# Ultrasonic_Receiver.net
KiCad netlist of a schematic drawn in Altium Designer
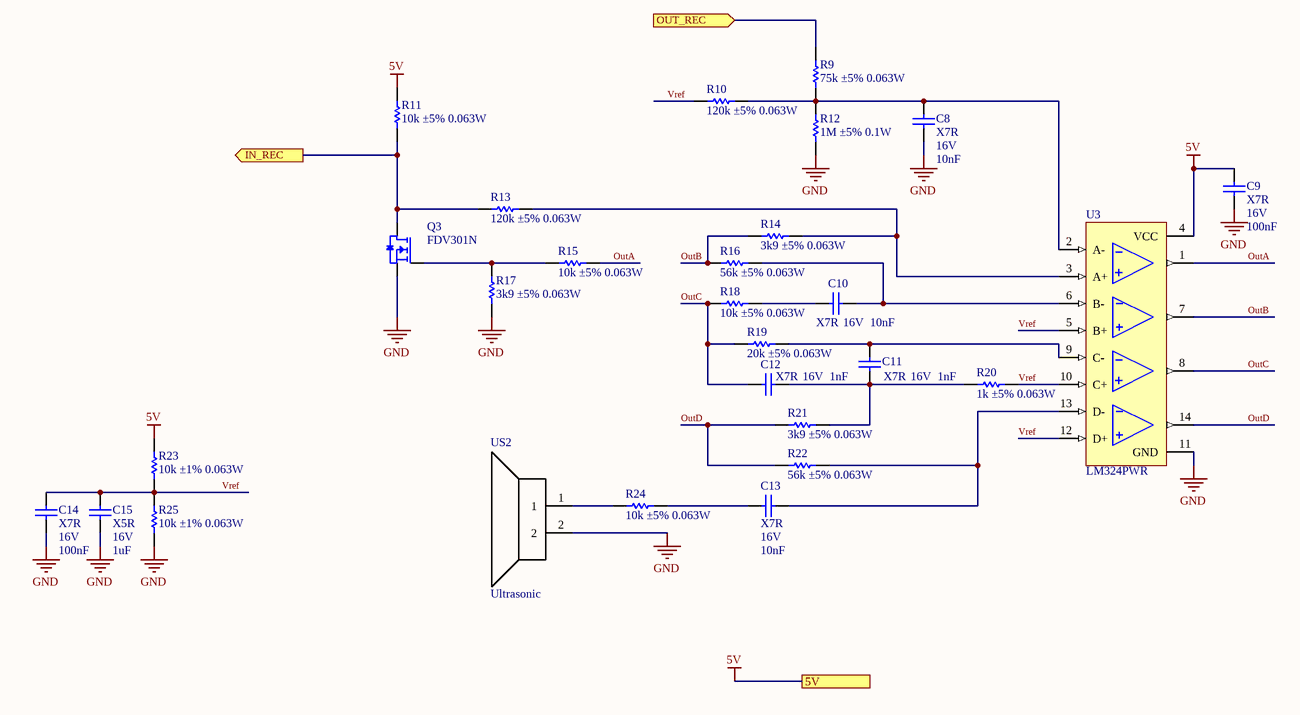
[diagram p0: Ultrasonic_Receiver.SchDoc]

(export (version "E")
  (design (tool "Eeschema 10.0.6"))
  (components
    (comp (ref "C8")
      (value "Capacitor")
      (footprint "C0402")
      (description "Capacitor SMD")
      (fields
        (field (name "DIELECTRIC") "X7R")
        (field (name "VOLTAGE") "16V")
        (field (name "CAPACITANCE") "10nF")
        (field (name "PART NUMBER") "C0402_10nF_16V_±10%")
        (field (name "TOLERANCE") "±10%")
      )
      (libsource (lib "Pasives_Capacitor_SMD") (part "Capacitor"))
    )
    (comp (ref "C9")
      (value "Capacitor")
      (footprint "C0402")
      (description "Capacitor SMD")
      (fields
        (field (name "DIELECTRIC") "X7R")
        (field (name "VOLTAGE") "16V")
        (field (name "CAPACITANCE") "100nF")
        (field (name "PART NUMBER") "C0402_100nF_16V_±10%")
        (field (name "TOLERANCE") "±10%")
      )
      (libsource (lib "Pasives_Capacitor_SMD") (part "Capacitor"))
    )
    (comp (ref "C10")
      (value "Capacitor")
      (footprint "C0402")
      (description "Capacitor SMD")
      (fields
        (field (name "DIELECTRIC") "X7R")
        (field (name "VOLTAGE") "16V")
        (field (name "CAPACITANCE") "10nF")
        (field (name "PART NUMBER") "C0402_10nF_16V_±10%")
        (field (name "TOLERANCE") "±10%")
      )
      (libsource (lib "Pasives_Capacitor_SMD") (part "Capacitor"))
    )
    (comp (ref "C11")
      (value "Capacitor")
      (footprint "C0402")
      (description "Capacitor SMD")
      (fields
        (field (name "DIELECTRIC") "X7R")
        (field (name "VOLTAGE") "16V")
        (field (name "CAPACITANCE") "1nF")
        (field (name "PART NUMBER") "C0402_1nF_16V_±10%")
        (field (name "TOLERANCE") "±10%")
      )
      (libsource (lib "Pasives_Capacitor_SMD") (part "Capacitor"))
    )
    (comp (ref "C12")
      (value "Capacitor")
      (footprint "C0402")
      (description "Capacitor SMD")
      (fields
        (field (name "DIELECTRIC") "X7R")
        (field (name "VOLTAGE") "16V")
        (field (name "CAPACITANCE") "1nF")
        (field (name "PART NUMBER") "C0402_1nF_16V_±10%")
        (field (name "TOLERANCE") "±10%")
      )
      (libsource (lib "Pasives_Capacitor_SMD") (part "Capacitor"))
    )
    (comp (ref "C13")
      (value "Capacitor")
      (footprint "C0402")
      (description "Capacitor SMD")
      (fields
        (field (name "DIELECTRIC") "X7R")
        (field (name "VOLTAGE") "16V")
        (field (name "CAPACITANCE") "10nF")
        (field (name "PART NUMBER") "C0402_10nF_16V_±10%")
        (field (name "TOLERANCE") "±10%")
      )
      (libsource (lib "Pasives_Capacitor_SMD") (part "Capacitor"))
    )
    (comp (ref "C14")
      (value "Capacitor")
      (footprint "C0402")
      (description "Capacitor SMD")
      (fields
        (field (name "DIELECTRIC") "X7R")
        (field (name "VOLTAGE") "16V")
        (field (name "CAPACITANCE") "100nF")
        (field (name "PART NUMBER") "C0402_100nF_16V_±10%")
        (field (name "TOLERANCE") "±10%")
      )
      (libsource (lib "Pasives_Capacitor_SMD") (part "Capacitor"))
    )
    (comp (ref "C15")
      (value "Capacitor")
      (footprint "C0603")
      (description "Capacitor SMD")
      (fields
        (field (name "DIELECTRIC") "X5R")
        (field (name "VOLTAGE") "16V")
        (field (name "CAPACITANCE") "1uF")
        (field (name "PART NUMBER") "C0603_1uF_16V_±10%")
        (field (name "TOLERANCE") "±10%")
      )
      (libsource (lib "Pasives_Capacitor_SMD") (part "Capacitor"))
    )
    (comp (ref "Q3")
      (value "FDV301N")
      (footprint "SOT23-3")
      (description "NFET")
      (fields (field (name "MANUFACTURER") "Fairchild Semiconductor"))
      (libsource (lib "Semiconductors_Transistors") (part "Mosfet_N"))
    )
    (comp (ref "R9")
      (value "75k ±5% 0.063W")
      (footprint "R0402")
      (description "Resistor, SMD")
      (fields (field (name "TOLERANCE") "±5%") (field (name "POWER") "0.063W"))
      (libsource (lib "Pasives_Resistor_SMD") (part "Resistor"))
    )
    (comp (ref "R10")
      (value "120k ±5% 0.063W")
      (footprint "R0402")
      (description "Resistor, SMD")
      (fields (field (name "TOLERANCE") "±5%") (field (name "POWER") "0.063W"))
      (libsource (lib "Pasives_Resistor_SMD") (part "Resistor"))
    )
    (comp (ref "R11")
      (value "10k ±5% 0.063W")
      (footprint "R0402")
      (description "Resistor, SMD")
      (fields (field (name "TOLERANCE") "±5%") (field (name "POWER") "0.063W"))
      (libsource (lib "Pasives_Resistor_SMD") (part "Resistor"))
    )
    (comp (ref "R12")
      (value "1M ±5% 0.1W")
      (footprint "R0603")
      (description "Resistor, SMD")
      (fields (field (name "TOLERANCE") "±5%") (field (name "POWER") "0.1W"))
      (libsource (lib "Pasives_Resistor_SMD") (part "Resistor"))
    )
    (comp (ref "R13")
      (value "120k ±5% 0.063W")
      (footprint "R0402")
      (description "Resistor, SMD")
      (fields (field (name "TOLERANCE") "±5%") (field (name "POWER") "0.063W"))
      (libsource (lib "Pasives_Resistor_SMD") (part "Resistor"))
    )
    (comp (ref "R14")
      (value "3k9 ±5% 0.063W")
      (footprint "R0402")
      (description "Resistor, SMD")
      (fields (field (name "TOLERANCE") "±5%") (field (name "POWER") "0.063W"))
      (libsource (lib "Pasives_Resistor_SMD") (part "Resistor"))
    )
    (comp (ref "R15")
      (value "10k ±5% 0.063W")
      (footprint "R0402")
      (description "Resistor, SMD")
      (fields (field (name "TOLERANCE") "±5%") (field (name "POWER") "0.063W"))
      (libsource (lib "Pasives_Resistor_SMD") (part "Resistor"))
    )
    (comp (ref "R16")
      (value "56k ±5% 0.063W")
      (footprint "R0402")
      (description "Resistor, SMD")
      (fields (field (name "TOLERANCE") "±5%") (field (name "POWER") "0.063W"))
      (libsource (lib "Pasives_Resistor_SMD") (part "Resistor"))
    )
    (comp (ref "R17")
      (value "3k9 ±5% 0.063W")
      (footprint "R0402")
      (description "Resistor, SMD")
      (fields (field (name "TOLERANCE") "±5%") (field (name "POWER") "0.063W"))
      (libsource (lib "Pasives_Resistor_SMD") (part "Resistor"))
    )
    (comp (ref "R18")
      (value "10k ±5% 0.063W")
      (footprint "R0402")
      (description "Resistor, SMD")
      (fields (field (name "TOLERANCE") "±5%") (field (name "POWER") "0.063W"))
      (libsource (lib "Pasives_Resistor_SMD") (part "Resistor"))
    )
    (comp (ref "R19")
      (value "20k ±5% 0.063W")
      (footprint "R0402")
      (description "Resistor, SMD")
      (fields (field (name "TOLERANCE") "±5%") (field (name "POWER") "0.063W"))
      (libsource (lib "Pasives_Resistor_SMD") (part "Resistor"))
    )
    (comp (ref "R20")
      (value "1k ±5% 0.063W")
      (footprint "R0402")
      (description "Resistor, SMD")
      (fields (field (name "TOLERANCE") "±5%") (field (name "POWER") "0.063W"))
      (libsource (lib "Pasives_Resistor_SMD") (part "Resistor"))
    )
    (comp (ref "R21")
      (value "3k9 ±5% 0.063W")
      (footprint "R0402")
      (description "Resistor, SMD")
      (fields (field (name "TOLERANCE") "±5%") (field (name "POWER") "0.063W"))
      (libsource (lib "Pasives_Resistor_SMD") (part "Resistor"))
    )
    (comp (ref "R22")
      (value "56k ±5% 0.063W")
      (footprint "R0402")
      (description "Resistor, SMD")
      (fields (field (name "TOLERANCE") "±5%") (field (name "POWER") "0.063W"))
      (libsource (lib "Pasives_Resistor_SMD") (part "Resistor"))
    )
    (comp (ref "R23")
      (value "10k ±1% 0.063W")
      (footprint "R0402")
      (description "Resistor, SMD")
      (fields (field (name "TOLERANCE") "±1%") (field (name "POWER") "0.063W"))
      (libsource (lib "Pasives_Resistor_SMD") (part "Resistor"))
    )
    (comp (ref "R24")
      (value "10k ±5% 0.063W")
      (footprint "R0402")
      (description "Resistor, SMD")
      (fields (field (name "TOLERANCE") "±5%") (field (name "POWER") "0.063W"))
      (libsource (lib "Pasives_Resistor_SMD") (part "Resistor"))
    )
    (comp (ref "R25")
      (value "10k ±1% 0.063W")
      (footprint "R0402")
      (description "Resistor, SMD")
      (fields (field (name "TOLERANCE") "±1%") (field (name "POWER") "0.063W"))
      (libsource (lib "Pasives_Resistor_SMD") (part "Resistor"))
    )
    (comp (ref "U3")
      (value "LM324PWR")
      (footprint "TSSOP14")
      (description "Operational Amplifier Quadruple")
      (fields (field (name "MANUFACTURER") "Texas Instruments"))
      (libsource (lib "Semiconductors_OA") (part "LM324PWR"))
    )
    (comp (ref "US2")
      (value "Ultrasonic")
      (footprint "NU40C16")
      (description "Ultrasonic Sensor")
      (fields (field (name "PART NUMBER") "NU40C16R-2") (field (name "MANUFACTURER") "Jinci"))
      (libsource (lib "Sensors") (part "Ultrasonic"))
    )
  )
  (nets
    (net (code "1") (name "/IN_REC") (class "Default")
      (node (ref "Q3") (pin "3") (pinfunction "D_3") (pintype "passive"))
      (node (ref "R11") (pin "1") (pinfunction "1_1") (pintype "passive"))
      (node (ref "R13") (pin "1") (pinfunction "1_1") (pintype "passive"))
    )
    (net (code "2") (name "/OUT_REC") (class "Default")
      (node (ref "R9") (pin "2") (pinfunction "2_2") (pintype "passive"))
    )
    (net (code "3") (name "/OutA") (class "Default")
      (node (ref "R15") (pin "1") (pinfunction "1_1") (pintype "passive"))
      (node (ref "U3") (pin "1") (pinfunction "OutA_1") (pintype "output"))
    )
    (net (code "4") (name "/OutB") (class "Default")
      (node (ref "R14") (pin "1") (pinfunction "1_1") (pintype "passive"))
      (node (ref "R16") (pin "1") (pinfunction "1_1") (pintype "passive"))
      (node (ref "U3") (pin "7") (pinfunction "OutB_7") (pintype "output"))
    )
    (net (code "5") (name "/OutC") (class "Default")
      (node (ref "C12") (pin "1") (pinfunction "1_1") (pintype "passive"))
      (node (ref "R18") (pin "2") (pinfunction "2_2") (pintype "passive"))
      (node (ref "R19") (pin "1") (pinfunction "1_1") (pintype "passive"))
      (node (ref "U3") (pin "8") (pinfunction "OutC_8") (pintype "output"))
    )
    (net (code "6") (name "/OutD") (class "Default")
      (node (ref "R21") (pin "1") (pinfunction "1_1") (pintype "passive"))
      (node (ref "R22") (pin "1") (pinfunction "1_1") (pintype "passive"))
      (node (ref "U3") (pin "14") (pinfunction "OutD_14") (pintype "output"))
    )
    (net (code "7") (name "/Vref") (class "Default")
      (node (ref "C14") (pin "2") (pinfunction "2_2") (pintype "passive"))
      (node (ref "C15") (pin "2") (pinfunction "2_2") (pintype "passive"))
      (node (ref "R10") (pin "1") (pinfunction "1_1") (pintype "passive"))
      (node (ref "R20") (pin "2") (pinfunction "2_2") (pintype "passive"))
      (node (ref "R23") (pin "1") (pinfunction "1_1") (pintype "passive"))
      (node (ref "R25") (pin "2") (pinfunction "2_2") (pintype "passive"))
      (node (ref "U3") (pin "10") (pinfunction "C+_10") (pintype "input"))
      (node (ref "U3") (pin "12") (pinfunction "D+_12") (pintype "input"))
      (node (ref "U3") (pin "5") (pinfunction "B+_5") (pintype "input"))
    )
    (net (code "8") (name "5V") (class "Default")
      (node (ref "C9") (pin "2") (pinfunction "2_2") (pintype "passive"))
      (node (ref "R11") (pin "2") (pinfunction "2_2") (pintype "passive"))
      (node (ref "R23") (pin "2") (pinfunction "2_2") (pintype "passive"))
      (node (ref "U3") (pin "4") (pinfunction "VCC_4") (pintype "power_in"))
    )
    (net (code "9") (name "GND") (class "Default")
      (node (ref "C14") (pin "1") (pinfunction "1_1") (pintype "passive"))
      (node (ref "C15") (pin "1") (pinfunction "1_1") (pintype "passive"))
      (node (ref "C8") (pin "1") (pinfunction "1_1") (pintype "passive"))
      (node (ref "C9") (pin "1") (pinfunction "1_1") (pintype "passive"))
      (node (ref "Q3") (pin "2") (pinfunction "S_2") (pintype "passive"))
      (node (ref "R12") (pin "1") (pinfunction "1_1") (pintype "passive"))
      (node (ref "R17") (pin "1") (pinfunction "1_1") (pintype "passive"))
      (node (ref "R25") (pin "1") (pinfunction "1_1") (pintype "passive"))
      (node (ref "U3") (pin "11") (pinfunction "GND_11") (pintype "power_in"))
      (node (ref "US2") (pin "2") (pinfunction "2_2") (pintype "passive"))
    )
    (net (code "10") (name "Net-(C10-Pad2)") (class "Default")
      (node (ref "C10") (pin "2") (pinfunction "2_2") (pintype "passive"))
      (node (ref "R18") (pin "1") (pinfunction "1_1") (pintype "passive"))
    )
    (net (code "11") (name "Net-(C11-Pad1)") (class "Default")
      (node (ref "C11") (pin "1") (pinfunction "1_1") (pintype "passive"))
      (node (ref "C12") (pin "2") (pinfunction "2_2") (pintype "passive"))
      (node (ref "R20") (pin "1") (pinfunction "1_1") (pintype "passive"))
      (node (ref "R21") (pin "2") (pinfunction "2_2") (pintype "passive"))
    )
    (net (code "12") (name "Net-(C13-Pad2)") (class "Default")
      (node (ref "C13") (pin "2") (pinfunction "2_2") (pintype "passive"))
      (node (ref "R24") (pin "1") (pinfunction "1_1") (pintype "passive"))
    )
    (net (code "13") (name "Net-(Q3-G)") (class "Default")
      (node (ref "Q3") (pin "1") (pinfunction "G_1") (pintype "passive"))
      (node (ref "R15") (pin "2") (pinfunction "2_2") (pintype "passive"))
      (node (ref "R17") (pin "2") (pinfunction "2_2") (pintype "passive"))
    )
    (net (code "14") (name "Net-(R24-Pad2)") (class "Default")
      (node (ref "R24") (pin "2") (pinfunction "2_2") (pintype "passive"))
      (node (ref "US2") (pin "1") (pinfunction "1_1") (pintype "passive"))
    )
    (net (code "15") (name "Net-(U3-A+)") (class "Default")
      (node (ref "R13") (pin "2") (pinfunction "2_2") (pintype "passive"))
      (node (ref "R14") (pin "2") (pinfunction "2_2") (pintype "passive"))
      (node (ref "U3") (pin "3") (pinfunction "A+_3") (pintype "input"))
    )
    (net (code "16") (name "Net-(U3-A-)") (class "Default")
      (node (ref "C8") (pin "2") (pinfunction "2_2") (pintype "passive"))
      (node (ref "R10") (pin "2") (pinfunction "2_2") (pintype "passive"))
      (node (ref "R12") (pin "2") (pinfunction "2_2") (pintype "passive"))
      (node (ref "R9") (pin "1") (pinfunction "1_1") (pintype "passive"))
      (node (ref "U3") (pin "2") (pinfunction "A-_2") (pintype "input"))
    )
    (net (code "17") (name "Net-(U3-B-)") (class "Default")
      (node (ref "C10") (pin "1") (pinfunction "1_1") (pintype "passive"))
      (node (ref "R16") (pin "2") (pinfunction "2_2") (pintype "passive"))
      (node (ref "U3") (pin "6") (pinfunction "B-_6") (pintype "input"))
    )
    (net (code "18") (name "Net-(U3-C-)") (class "Default")
      (node (ref "C11") (pin "2") (pinfunction "2_2") (pintype "passive"))
      (node (ref "R19") (pin "2") (pinfunction "2_2") (pintype "passive"))
      (node (ref "U3") (pin "9") (pinfunction "C-_9") (pintype "input"))
    )
    (net (code "19") (name "Net-(U3-D-)") (class "Default")
      (node (ref "C13") (pin "1") (pinfunction "1_1") (pintype "passive"))
      (node (ref "R22") (pin "2") (pinfunction "2_2") (pintype "passive"))
      (node (ref "U3") (pin "13") (pinfunction "D-_13") (pintype "input"))
    )
  )
)
